# isolation.net
KiCad netlist of a schematic drawn in Altium Designer
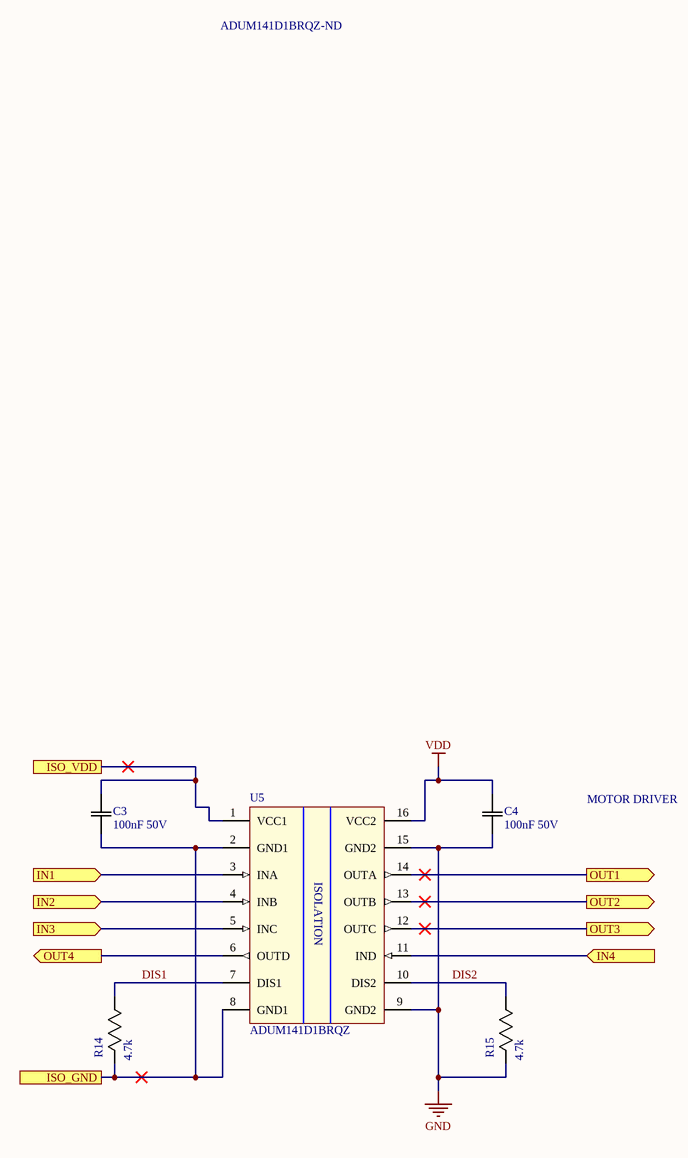
[diagram p0: isolation.SchDoc]

(export (version "E")
  (design (tool "Eeschema 10.0.6"))
  (components
    (comp (ref "C3")
      (value "100nF 50V")
      (footprint "0603")
      (description "Default Symbol for Capacitors")
      (fields (field (name "PART NUMBER") "CAP 100nF 50V") (field (name "TOLERANCE") "10%"))
      (libsource (lib "capacitor_library") (part "CAP_Default"))
    )
    (comp (ref "C4")
      (value "100nF 50V")
      (footprint "0603")
      (description "Default Symbol for Capacitors")
      (fields (field (name "PART NUMBER") "CAP 100nF 50V") (field (name "TOLERANCE") "10%"))
      (libsource (lib "capacitor_library") (part "CAP_Default"))
    )
    (comp (ref "R14")
      (value "4.7k")
      (footprint "0603")
      (description "Default Resistor Symbol")
      (fields (field (name "TOLERANCE") "5%") (field (name "PART NUMBER") "RES 4.7k 1/8W - 5%"))
      (libsource (lib "Resistor_Library") (part "RES_DEFAULT"))
    )
    (comp (ref "R15")
      (value "4.7k")
      (footprint "0603")
      (description "Default Resistor Symbol")
      (fields (field (name "TOLERANCE") "5%") (field (name "PART NUMBER") "RES 4.7k 1/8W - 5%"))
      (libsource (lib "Resistor_Library") (part "RES_DEFAULT"))
    )
    (comp (ref "U5")
      (value "ADUM141D1BRQZ")
      (footprint "SOP64P600X175-16N")
      (description "Digital Isolator CMOS 4-CH 150Mbps 16-Pin QSOP T/R")
      (fields
        (field (name "SUPPLIER PART NUMBER 1") "ADUM141D1BRQZ-ND")
        (field (name "PART NUMBER") "ISO ADUM141D1BRQZ")
      )
      (libsource (lib "IC_Library") (part "ISO ADUM141D1BRQZ"))
    )
  )
  (nets
    (net (code "1") (name "/DIS1") (class "Default")
      (node (ref "R14") (pin "1") (pinfunction "R1_1") (pintype "passive"))
      (node (ref "U5") (pin "7") (pinfunction "DIS1_7") (pintype "passive"))
    )
    (net (code "2") (name "/DIS2") (class "Default")
      (node (ref "R15") (pin "1") (pinfunction "R1_1") (pintype "passive"))
      (node (ref "U5") (pin "10") (pinfunction "DIS2_10") (pintype "passive"))
    )
    (net (code "3") (name "/IN1") (class "Default")
      (node (ref "U5") (pin "3") (pinfunction "INA_3") (pintype "input"))
    )
    (net (code "4") (name "/IN2") (class "Default")
      (node (ref "U5") (pin "4") (pinfunction "INB_4") (pintype "input"))
    )
    (net (code "5") (name "/IN3") (class "Default")
      (node (ref "U5") (pin "5") (pinfunction "INC_5") (pintype "input"))
    )
    (net (code "6") (name "/IN4") (class "Default")
      (node (ref "U5") (pin "11") (pinfunction "IND_11") (pintype "input"))
    )
    (net (code "7") (name "/ISO_GND") (class "Default")
      (node (ref "C3") (pin "1") (pinfunction "C1_1") (pintype "passive"))
      (node (ref "R14") (pin "2") (pinfunction "R2_2") (pintype "passive"))
      (node (ref "U5") (pin "2") (pinfunction "GND1_2") (pintype "power_in"))
      (node (ref "U5") (pin "8") (pinfunction "GND1_8") (pintype "power_in"))
    )
    (net (code "8") (name "/ISO_VDD") (class "Default")
      (node (ref "C3") (pin "2") (pinfunction "C2_2") (pintype "passive"))
      (node (ref "U5") (pin "1") (pinfunction "VCC1_1") (pintype "power_in"))
    )
    (net (code "9") (name "/OUT1") (class "Default")
      (node (ref "U5") (pin "14") (pinfunction "OUTA_14") (pintype "output"))
    )
    (net (code "10") (name "/OUT2") (class "Default")
      (node (ref "U5") (pin "13") (pinfunction "OUTB_13") (pintype "output"))
    )
    (net (code "11") (name "/OUT3") (class "Default")
      (node (ref "U5") (pin "12") (pinfunction "OUTC_12") (pintype "output"))
    )
    (net (code "12") (name "/OUT4") (class "Default")
      (node (ref "U5") (pin "6") (pinfunction "OUTD_6") (pintype "output"))
    )
    (net (code "13") (name "GND") (class "Default")
      (node (ref "C4") (pin "1") (pinfunction "C1_1") (pintype "passive"))
      (node (ref "R15") (pin "2") (pinfunction "R2_2") (pintype "passive"))
      (node (ref "U5") (pin "15") (pinfunction "GND2_15") (pintype "power_in"))
      (node (ref "U5") (pin "9") (pinfunction "GND2_9") (pintype "power_in"))
    )
    (net (code "14") (name "VDD") (class "Default")
      (node (ref "C4") (pin "2") (pinfunction "C2_2") (pintype "passive"))
      (node (ref "U5") (pin "16") (pinfunction "VCC2_16") (pintype "power_in"))
    )
  )
)
